# SirenSchematic.net
KiCad netlist of a schematic drawn in Altium Designer
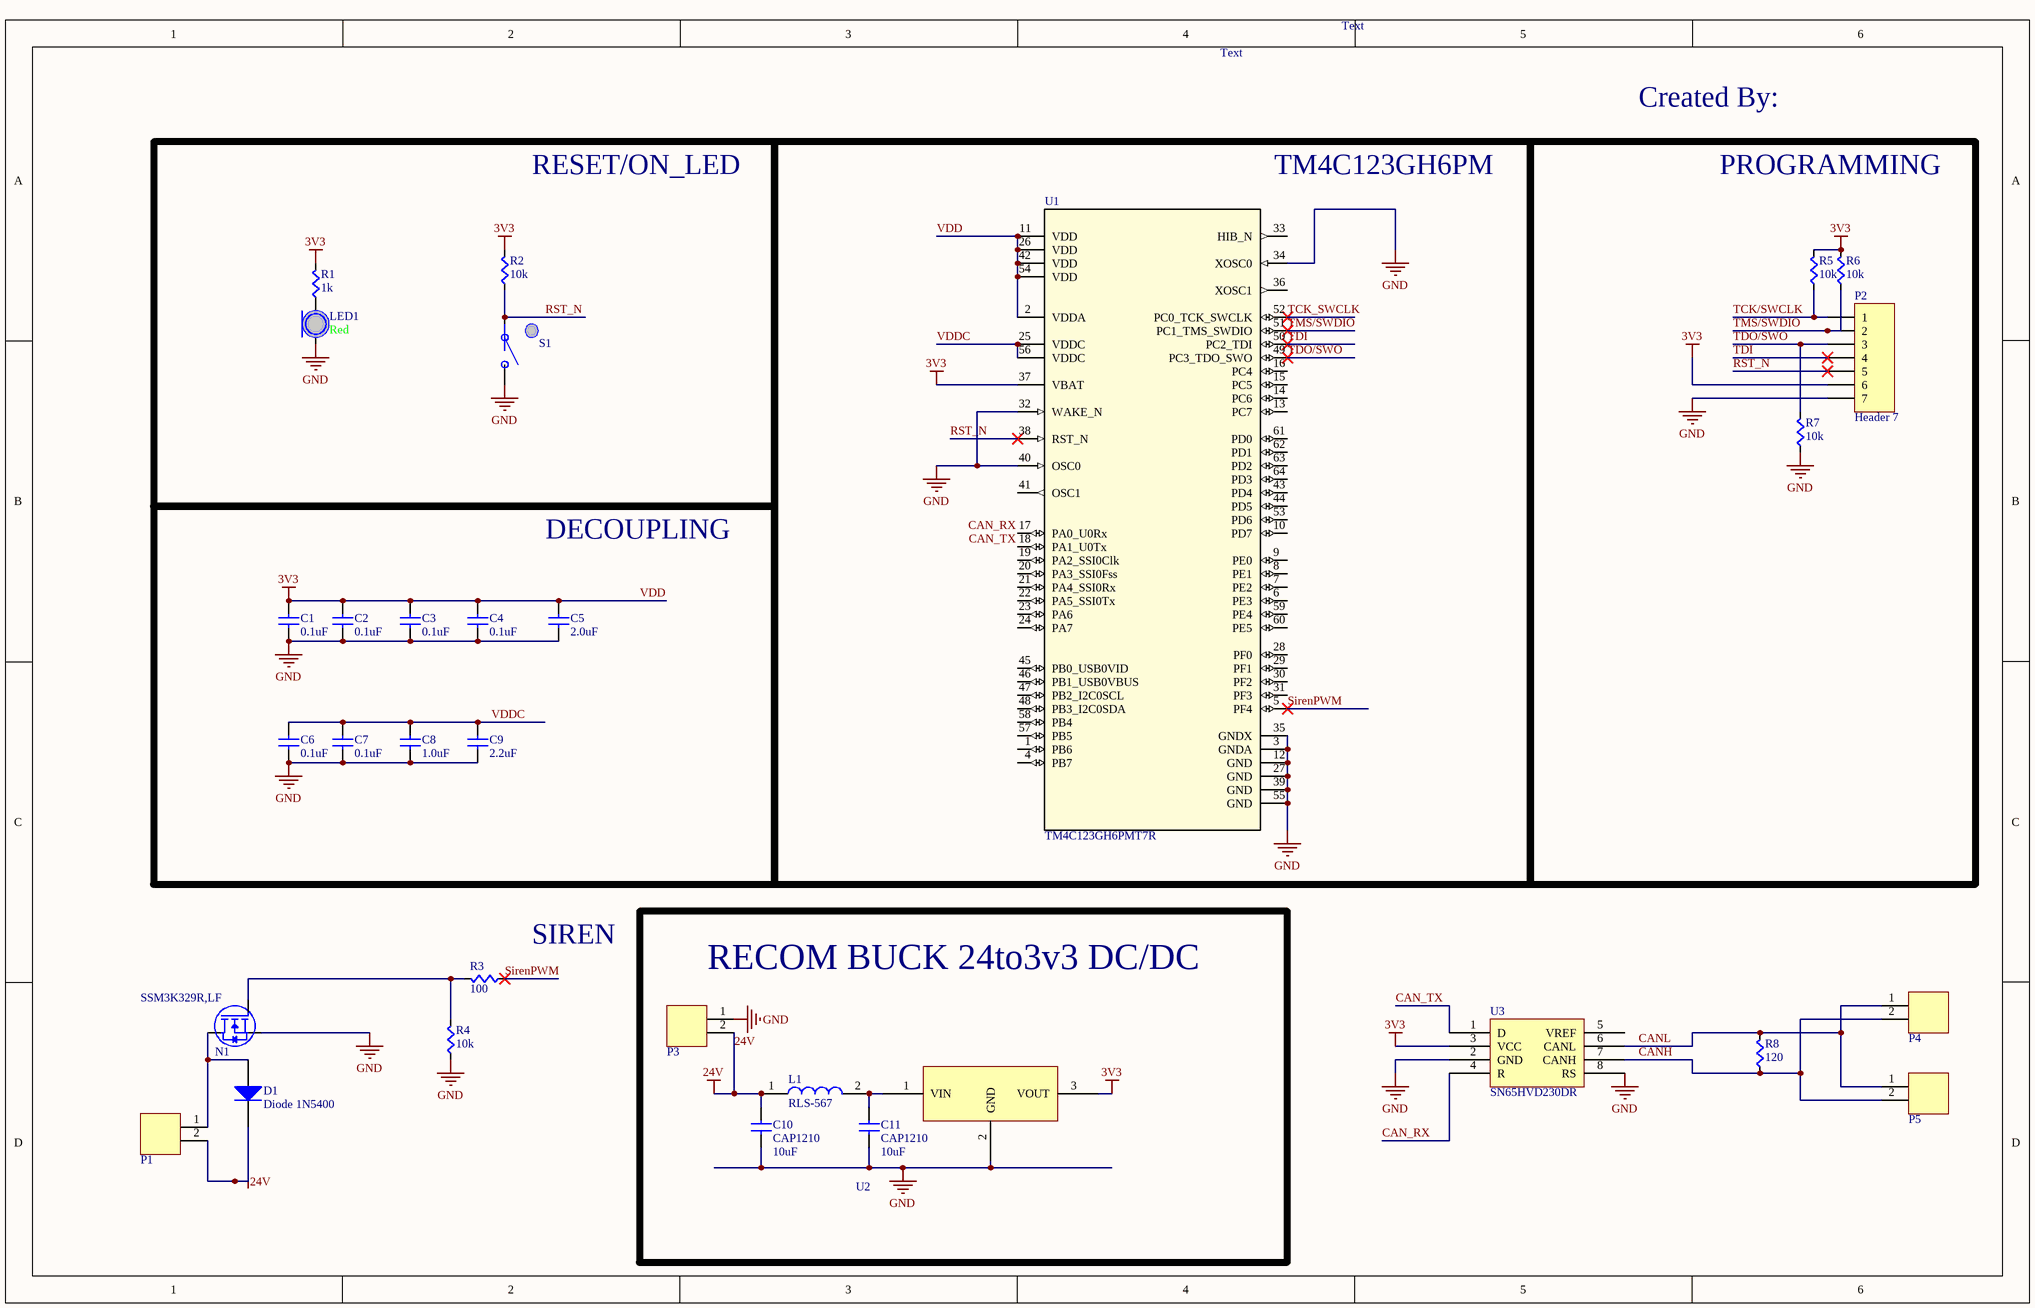
[diagram p0: SirenSchematic.SchDoc]

(export (version "E")
  (design (tool "Eeschema 10.0.6"))
  (components
    (comp (ref "C1")
      (value "0.1uF")
      (footprint "CAPC0603")
      (fields (field (name "Comment") "Cap"))
      (libsource (lib "SubjuGator8") (part "Cap"))
    )
    (comp (ref "C2")
      (value "0.1uF")
      (footprint "CAPC0603")
      (fields (field (name "Comment") "Cap"))
      (libsource (lib "SubjuGator8") (part "Cap"))
    )
    (comp (ref "C3")
      (value "0.1uF")
      (footprint "CAPC0603")
      (fields (field (name "Comment") "Cap"))
      (libsource (lib "SubjuGator8") (part "Cap"))
    )
    (comp (ref "C4")
      (value "0.1uF")
      (footprint "CAPC0603")
      (fields (field (name "Comment") "Cap"))
      (libsource (lib "SubjuGator8") (part "Cap"))
    )
    (comp (ref "C5")
      (value "2.0uF")
      (footprint "CAPC0603")
      (fields (field (name "Comment") "Cap"))
      (libsource (lib "SubjuGator8") (part "Cap"))
    )
    (comp (ref "C6")
      (value "0.1uF")
      (footprint "CAPC0603")
      (fields (field (name "Comment") "Cap"))
      (libsource (lib "SubjuGator8") (part "Cap"))
    )
    (comp (ref "C7")
      (value "0.1uF")
      (footprint "CAPC0603")
      (fields (field (name "Comment") "Cap"))
      (libsource (lib "SubjuGator8") (part "Cap"))
    )
    (comp (ref "C8")
      (value "1.0uF")
      (footprint "CAPC0603")
      (fields (field (name "Comment") "Cap"))
      (libsource (lib "SubjuGator8") (part "Cap"))
    )
    (comp (ref "C9")
      (value "2.2uF")
      (footprint "CAPC0603")
      (fields (field (name "Comment") "Cap"))
      (libsource (lib "SubjuGator8") (part "Cap"))
    )
    (comp (ref "C10")
      (value "CAP1210")
      (footprint "CAP1210")
      (description "CAP CER 10UF 50V 20% X5R 1210")
      (fields (field (name "ALTIUM_VALUE") "10uF"))
      (libsource (lib "SubjuGator8") (part "CAP1210"))
    )
    (comp (ref "C11")
      (value "CAP1210")
      (footprint "CAP1210")
      (description "CAP CER 10UF 50V 20% X5R 1210")
      (fields (field (name "ALTIUM_VALUE") "10uF"))
      (libsource (lib "SubjuGator8") (part "CAP1210"))
    )
    (comp (ref "D1")
      (value "Diode 1N5400")
      (footprint "DO-201AD")
      (description "3 Amp General Purpose Rectifier")
      (fields (field (name "PUBLISHER") "Altium Limited"))
      (libsource (lib "Miscellaneous Devices") (part "Diode 1N5400"))
    )
    (comp (ref "L1")
      (value "RLS-567")
      (footprint "*IND_RLS-567")
      (description "Inductor")
      (fields (field (name "MOUSER PART NUMBER") "919-RLS-567"))
      (libsource (lib "SubjuGator8") (part "RLS-567"))
    )
    (comp (ref "LED1")
      (value "LED")
      (footprint "LED0603")
      (fields (field (name "COLOR") "Red"))
      (libsource (lib "SubjuGator8") (part "LED"))
    )
    (comp (ref "N1")
      (value "SSM3K329R,LF")
      (footprint "SSM3K329R,LF")
      (description "MOSFET N CH 30V 3.5A 2-3Z1A")
      (libsource (lib "SubjuGator8") (part "SSM3K329R,LF"))
    )
    (comp (ref "P1")
      (value "2-pin Horz Sherlock")
      (footprint "MOLEX-HDR-1X2-SHERLOCK-HORZ")
      (fields
        (field (name "MANUFACTURER PART NUMBER") "0353630260")
        (field (name "MANUFACTURER") "Molex Inc")
      )
      (libsource (lib "SubjuGator8") (part "MOLEX-HDR-1x2-SHERLOCK_RA"))
    )
    (comp (ref "P2")
      (value "Header 7")
      (footprint "HDR1X7")
      (description "Header, 7-Pin")
      (fields (field (name "PUBLISHER") "Altium Limited"))
      (libsource (lib "Miscellaneous Connectors") (part "Header 7"))
    )
    (comp (ref "P3")
      (value "2-pin Horz Sherlock")
      (footprint "MOLEX-HDR-1X2-SHERLOCK-HORZ")
      (fields
        (field (name "MANUFACTURER PART NUMBER") "0353630260")
        (field (name "MANUFACTURER") "Molex Inc")
      )
      (libsource (lib "SubjuGator8") (part "MOLEX-HDR-1x2-SHERLOCK_RA"))
    )
    (comp (ref "P4")
      (value "2-pin Horz Sherlock")
      (footprint "MOLEX-HDR-1X2-SHERLOCK-HORZ")
      (fields
        (field (name "MANUFACTURER PART NUMBER") "0353630260")
        (field (name "MANUFACTURER") "Molex Inc")
      )
      (libsource (lib "") (part "MOLEX-HDR-1x2-SHERLOCK_RA_1"))
    )
    (comp (ref "P5")
      (value "2-pin Horz Sherlock")
      (footprint "MOLEX-HDR-1X2-SHERLOCK-HORZ")
      (fields
        (field (name "MANUFACTURER PART NUMBER") "0353630260")
        (field (name "MANUFACTURER") "Molex Inc")
      )
      (libsource (lib "") (part "MOLEX-HDR-1x2-SHERLOCK_RA_1"))
    )
    (comp (ref "R1")
      (value "1k")
      (footprint "RES0603")
      (fields (field (name "Comment") "Res"))
      (libsource (lib "SubjuGator8") (part "Res"))
    )
    (comp (ref "R2")
      (value "10k")
      (footprint "RES0603")
      (fields (field (name "Comment") "Res"))
      (libsource (lib "SubjuGator8") (part "Res"))
    )
    (comp (ref "R3")
      (value "100")
      (footprint "RES0603")
      (fields (field (name "Comment") "Res"))
      (libsource (lib "SubjuGator8") (part "Res"))
    )
    (comp (ref "R4")
      (value "10k")
      (footprint "RES0603")
      (fields (field (name "Comment") "Res"))
      (libsource (lib "SubjuGator8") (part "Res"))
    )
    (comp (ref "R5")
      (value "10k")
      (footprint "RES0603")
      (fields (field (name "Comment") "Res"))
      (libsource (lib "SubjuGator8") (part "Res"))
    )
    (comp (ref "R6")
      (value "10k")
      (footprint "RES0603")
      (fields (field (name "Comment") "Res"))
      (libsource (lib "SubjuGator8") (part "Res"))
    )
    (comp (ref "R7")
      (value "10k")
      (footprint "RES0603")
      (fields (field (name "Comment") "Res"))
      (libsource (lib "SubjuGator8") (part "Res"))
    )
    (comp (ref "R8")
      (value "120")
      (footprint "RES0603")
      (fields (field (name "Comment") "Res"))
      (libsource (lib "SubjuGator8") (part "Res"))
    )
    (comp (ref "S1")
      (value "Button")
      (footprint "PTS645xxxxSMTR92")
      (description "SPST Button")
      (libsource (lib "SubjuGator8") (part "Button"))
    )
    (comp (ref "U1")
      (value "TM4C123GH6PMT7R")
      (footprint "PM0064A_N")
      (description "Imported")
      (fields
        (field (name "PARTNUMBER") "TM4C123GH6PMTR")
        (field (name "ALTERNATE_PARTNUMBER") "TM4C123GH6PMT")
      )
      (libsource (lib "2018-10-31_17-53-54") (part "TM4C123GH6PMT7R"))
    )
    (comp (ref "U2")
      (value "R-78C3.3-1.0")
      (footprint "R-78C3.3-1.0")
      (description "CONV DC/DC 1A 3.3V OUT SIP VERT")
      (libsource (lib "SubjuGator8") (part "R-78C3.3-1.0"))
    )
    (comp (ref "U3")
      (value "SN65HVD230DR")
      (footprint "SOIC-8pin")
      (description "IC TXRX CAN 1MBPS 3.3V 8SOIC")
      (libsource (lib "SubjuGator8") (part "SN65HVD230DR"))
    )
  )
  (nets
    (net (code "1") (name "/CANH") (class "Default")
      (node (ref "P4") (pin "2") (pinfunction "2_2") (pintype "passive"))
      (node (ref "P5") (pin "2") (pinfunction "2_2") (pintype "passive"))
      (node (ref "R8") (pin "2") (pinfunction "B_2") (pintype "passive"))
      (node (ref "U3") (pin "7") (pinfunction "CANH_7") (pintype "passive"))
    )
    (net (code "2") (name "/CANL") (class "Default")
      (node (ref "P4") (pin "1") (pinfunction "1_1") (pintype "passive"))
      (node (ref "P5") (pin "1") (pinfunction "1_1") (pintype "passive"))
      (node (ref "R8") (pin "1") (pinfunction "A_1") (pintype "passive"))
      (node (ref "U3") (pin "6") (pinfunction "CANL_6") (pintype "passive"))
    )
    (net (code "3") (name "/CAN_RX") (class "Default")
      (node (ref "U1") (pin "17") (pinfunction "PA0_U0Rx_17") (pintype "bidirectional"))
      (node (ref "U3") (pin "4") (pinfunction "R_4") (pintype "passive"))
    )
    (net (code "4") (name "/CAN_TX") (class "Default")
      (node (ref "U1") (pin "18") (pinfunction "PA1_U0Tx_18") (pintype "bidirectional"))
      (node (ref "U3") (pin "1") (pinfunction "D_1") (pintype "passive"))
    )
    (net (code "5") (name "/RST_N") (class "Default")
      (node (ref "P2") (pin "5") (pinfunction "5_5") (pintype "passive"))
      (node (ref "R2") (pin "2") (pinfunction "B_2") (pintype "passive"))
      (node (ref "S1") (pin "A") (pinfunction "A_A") (pintype "passive"))
      (node (ref "U1") (pin "38") (pinfunction "RST_N_38") (pintype "input"))
    )
    (net (code "6") (name "/SirenPWM") (class "Default")
      (node (ref "R3") (pin "2") (pinfunction "B_2") (pintype "passive"))
      (node (ref "U1") (pin "5") (pinfunction "PF4_5") (pintype "bidirectional"))
    )
    (net (code "7") (name "/TCK_SWCLK") (class "Default")
      (node (ref "U1") (pin "52") (pinfunction "PC0_TCK_SWCLK_52") (pintype "bidirectional+no_connect"))
    )
    (net (code "8") (name "/TCK{slash}SWCLK") (class "Default")
      (node (ref "P2") (pin "1") (pinfunction "1_1") (pintype "passive"))
      (node (ref "R5") (pin "2") (pinfunction "B_2") (pintype "passive"))
    )
    (net (code "9") (name "/TDI") (class "Default")
      (node (ref "P2") (pin "4") (pinfunction "4_4") (pintype "passive"))
      (node (ref "U1") (pin "50") (pinfunction "PC2_TDI_50") (pintype "bidirectional"))
    )
    (net (code "10") (name "/TDO{slash}SWO") (class "Default")
      (node (ref "P2") (pin "3") (pinfunction "3_3") (pintype "passive"))
      (node (ref "R7") (pin "1") (pinfunction "A_1") (pintype "passive"))
      (node (ref "U1") (pin "49") (pinfunction "PC3_TDO_SWO_49") (pintype "bidirectional"))
    )
    (net (code "11") (name "/TMS{slash}SWDIO") (class "Default")
      (node (ref "P2") (pin "2") (pinfunction "2_2") (pintype "passive"))
      (node (ref "R6") (pin "2") (pinfunction "B_2") (pintype "passive"))
      (node (ref "U1") (pin "51") (pinfunction "PC1_TMS_SWDIO_51") (pintype "bidirectional"))
    )
    (net (code "12") (name "/VDDC") (class "Default")
      (node (ref "C6") (pin "1") (pinfunction "A_1") (pintype "passive"))
      (node (ref "C7") (pin "1") (pinfunction "A_1") (pintype "passive"))
      (node (ref "C8") (pin "1") (pinfunction "A_1") (pintype "passive"))
      (node (ref "C9") (pin "1") (pinfunction "A_1") (pintype "passive"))
      (node (ref "U1") (pin "25") (pinfunction "VDDC_25") (pintype "power_in"))
      (node (ref "U1") (pin "56") (pinfunction "VDDC_56") (pintype "power_in"))
    )
    (net (code "13") (name "3V3") (class "Default")
      (node (ref "C1") (pin "1") (pinfunction "A_1") (pintype "passive"))
      (node (ref "C2") (pin "1") (pinfunction "A_1") (pintype "passive"))
      (node (ref "C3") (pin "1") (pinfunction "A_1") (pintype "passive"))
      (node (ref "C4") (pin "1") (pinfunction "A_1") (pintype "passive"))
      (node (ref "C5") (pin "1") (pinfunction "A_1") (pintype "passive"))
      (node (ref "P2") (pin "6") (pinfunction "6_6") (pintype "passive"))
      (node (ref "R1") (pin "1") (pinfunction "A_1") (pintype "passive"))
      (node (ref "R2") (pin "1") (pinfunction "A_1") (pintype "passive"))
      (node (ref "R5") (pin "1") (pinfunction "A_1") (pintype "passive"))
      (node (ref "R6") (pin "1") (pinfunction "A_1") (pintype "passive"))
      (node (ref "U1") (pin "11") (pinfunction "VDD_11") (pintype "power_in"))
      (node (ref "U1") (pin "2") (pinfunction "VDDA_2") (pintype "power_in"))
      (node (ref "U1") (pin "26") (pinfunction "VDD_26") (pintype "power_in"))
      (node (ref "U1") (pin "37") (pinfunction "VBAT_37") (pintype "power_in"))
      (node (ref "U1") (pin "42") (pinfunction "VDD_42") (pintype "power_in"))
      (node (ref "U1") (pin "54") (pinfunction "VDD_54") (pintype "power_in"))
      (node (ref "U2") (pin "3") (pinfunction "VOUT_3") (pintype "passive"))
      (node (ref "U3") (pin "3") (pinfunction "VCC_3") (pintype "passive"))
    )
    (net (code "14") (name "24V") (class "Default")
      (node (ref "C10") (pin "1") (pinfunction "A_1") (pintype "passive"))
      (node (ref "D1") (pin "2") (pinfunction "K_2") (pintype "passive"))
      (node (ref "L1") (pin "1") (pinfunction "1_1") (pintype "passive"))
      (node (ref "P1") (pin "2") (pinfunction "2_2") (pintype "passive"))
      (node (ref "P3") (pin "2") (pinfunction "2_2") (pintype "passive"))
    )
    (net (code "15") (name "GND") (class "Default")
      (node (ref "C1") (pin "2") (pinfunction "B_2") (pintype "passive"))
      (node (ref "C10") (pin "2") (pinfunction "B_2") (pintype "passive"))
      (node (ref "C11") (pin "2") (pinfunction "B_2") (pintype "passive"))
      (node (ref "C2") (pin "2") (pinfunction "B_2") (pintype "passive"))
      (node (ref "C3") (pin "2") (pinfunction "B_2") (pintype "passive"))
      (node (ref "C4") (pin "2") (pinfunction "B_2") (pintype "passive"))
      (node (ref "C5") (pin "2") (pinfunction "B_2") (pintype "passive"))
      (node (ref "C6") (pin "2") (pinfunction "B_2") (pintype "passive"))
      (node (ref "C7") (pin "2") (pinfunction "B_2") (pintype "passive"))
      (node (ref "C8") (pin "2") (pinfunction "B_2") (pintype "passive"))
      (node (ref "C9") (pin "2") (pinfunction "B_2") (pintype "passive"))
      (node (ref "LED1") (pin "C") (pinfunction "C_C") (pintype "passive"))
      (node (ref "N1") (pin "2") (pinfunction "S_2") (pintype "passive"))
      (node (ref "P2") (pin "7") (pinfunction "7_7") (pintype "passive"))
      (node (ref "P3") (pin "1") (pinfunction "1_1") (pintype "passive"))
      (node (ref "R4") (pin "2") (pinfunction "B_2") (pintype "passive"))
      (node (ref "R7") (pin "2") (pinfunction "B_2") (pintype "passive"))
      (node (ref "S1") (pin "B") (pinfunction "B_B") (pintype "passive"))
      (node (ref "U1") (pin "12") (pinfunction "GND_12") (pintype "power_in"))
      (node (ref "U1") (pin "27") (pinfunction "GND_27") (pintype "power_in"))
      (node (ref "U1") (pin "3") (pinfunction "GNDA_3") (pintype "power_in"))
      (node (ref "U1") (pin "32") (pinfunction "WAKE_N_32") (pintype "input"))
      (node (ref "U1") (pin "34") (pinfunction "XOSC0_34") (pintype "input"))
      (node (ref "U1") (pin "35") (pinfunction "GNDX_35") (pintype "power_in"))
      (node (ref "U1") (pin "39") (pinfunction "GND_39") (pintype "power_in"))
      (node (ref "U1") (pin "40") (pinfunction "OSC0_40") (pintype "input"))
      (node (ref "U1") (pin "55") (pinfunction "GND_55") (pintype "power_in"))
      (node (ref "U2") (pin "2") (pinfunction "GND_2") (pintype "power_in"))
      (node (ref "U3") (pin "2") (pinfunction "GND_2") (pintype "passive"))
      (node (ref "U3") (pin "8") (pinfunction "RS_8") (pintype "passive"))
    )
    (net (code "16") (name "Net-(C11-A)") (class "Default")
      (node (ref "C11") (pin "1") (pinfunction "A_1") (pintype "passive"))
      (node (ref "L1") (pin "2") (pinfunction "2_2") (pintype "passive"))
      (node (ref "U2") (pin "1") (pinfunction "VIN_1") (pintype "passive"))
    )
    (net (code "17") (name "Net-(D1-A)") (class "Default")
      (node (ref "D1") (pin "1") (pinfunction "A_1") (pintype "passive"))
      (node (ref "N1") (pin "3") (pinfunction "D_3") (pintype "passive"))
      (node (ref "P1") (pin "1") (pinfunction "1_1") (pintype "passive"))
    )
    (net (code "18") (name "Net-(N1-G)") (class "Default")
      (node (ref "N1") (pin "1") (pinfunction "G_1") (pintype "passive"))
      (node (ref "R3") (pin "1") (pinfunction "A_1") (pintype "passive"))
      (node (ref "R4") (pin "1") (pinfunction "A_1") (pintype "passive"))
    )
    (net (code "19") (name "Net-(R1-B)") (class "Default")
      (node (ref "LED1") (pin "A") (pinfunction "A_A") (pintype "passive"))
      (node (ref "R1") (pin "2") (pinfunction "B_2") (pintype "passive"))
    )
    (net (code "20") (name "unconnected-(U1-HIB_N-Pad33)") (class "Default")
      (node (ref "U1") (pin "33") (pinfunction "HIB_N_33") (pintype "output"))
    )
    (net (code "21") (name "unconnected-(U1-OSC1-Pad41)") (class "Default")
      (node (ref "U1") (pin "41") (pinfunction "OSC1_41") (pintype "output"))
    )
    (net (code "22") (name "unconnected-(U1-PA2_SSI0Clk-Pad19)") (class "Default")
      (node (ref "U1") (pin "19") (pinfunction "PA2_SSI0Clk_19") (pintype "bidirectional"))
    )
    (net (code "23") (name "unconnected-(U1-PA3_SSI0Fss-Pad20)") (class "Default")
      (node (ref "U1") (pin "20") (pinfunction "PA3_SSI0Fss_20") (pintype "bidirectional"))
    )
    (net (code "24") (name "unconnected-(U1-PA4_SSI0Rx-Pad21)") (class "Default")
      (node (ref "U1") (pin "21") (pinfunction "PA4_SSI0Rx_21") (pintype "bidirectional"))
    )
    (net (code "25") (name "unconnected-(U1-PA5_SSI0Tx-Pad22)") (class "Default")
      (node (ref "U1") (pin "22") (pinfunction "PA5_SSI0Tx_22") (pintype "bidirectional"))
    )
    (net (code "26") (name "unconnected-(U1-PA6-Pad23)") (class "Default")
      (node (ref "U1") (pin "23") (pinfunction "PA6_23") (pintype "bidirectional"))
    )
    (net (code "27") (name "unconnected-(U1-PA7-Pad24)") (class "Default")
      (node (ref "U1") (pin "24") (pinfunction "PA7_24") (pintype "bidirectional"))
    )
    (net (code "28") (name "unconnected-(U1-PB0_USB0VID-Pad45)") (class "Default")
      (node (ref "U1") (pin "45") (pinfunction "PB0_USB0VID_45") (pintype "bidirectional"))
    )
    (net (code "29") (name "unconnected-(U1-PB1_USB0VBUS-Pad46)") (class "Default")
      (node (ref "U1") (pin "46") (pinfunction "PB1_USB0VBUS_46") (pintype "bidirectional"))
    )
    (net (code "30") (name "unconnected-(U1-PB2_I2C0SCL-Pad47)") (class "Default")
      (node (ref "U1") (pin "47") (pinfunction "PB2_I2C0SCL_47") (pintype "bidirectional"))
    )
    (net (code "31") (name "unconnected-(U1-PB3_I2C0SDA-Pad48)") (class "Default")
      (node (ref "U1") (pin "48") (pinfunction "PB3_I2C0SDA_48") (pintype "bidirectional"))
    )
    (net (code "32") (name "unconnected-(U1-PB4-Pad58)") (class "Default")
      (node (ref "U1") (pin "58") (pinfunction "PB4_58") (pintype "bidirectional"))
    )
    (net (code "33") (name "unconnected-(U1-PB5-Pad57)") (class "Default")
      (node (ref "U1") (pin "57") (pinfunction "PB5_57") (pintype "bidirectional"))
    )
    (net (code "34") (name "unconnected-(U1-PB6-Pad1)") (class "Default")
      (node (ref "U1") (pin "1") (pinfunction "PB6_1") (pintype "bidirectional"))
    )
    (net (code "35") (name "unconnected-(U1-PB7-Pad4)") (class "Default")
      (node (ref "U1") (pin "4") (pinfunction "PB7_4") (pintype "bidirectional"))
    )
    (net (code "36") (name "unconnected-(U1-PC4-Pad16)") (class "Default")
      (node (ref "U1") (pin "16") (pinfunction "PC4_16") (pintype "bidirectional"))
    )
    (net (code "37") (name "unconnected-(U1-PC5-Pad15)") (class "Default")
      (node (ref "U1") (pin "15") (pinfunction "PC5_15") (pintype "bidirectional"))
    )
    (net (code "38") (name "unconnected-(U1-PC6-Pad14)") (class "Default")
      (node (ref "U1") (pin "14") (pinfunction "PC6_14") (pintype "bidirectional"))
    )
    (net (code "39") (name "unconnected-(U1-PC7-Pad13)") (class "Default")
      (node (ref "U1") (pin "13") (pinfunction "PC7_13") (pintype "bidirectional"))
    )
    (net (code "40") (name "unconnected-(U1-PD0-Pad61)") (class "Default")
      (node (ref "U1") (pin "61") (pinfunction "PD0_61") (pintype "bidirectional"))
    )
    (net (code "41") (name "unconnected-(U1-PD1-Pad62)") (class "Default")
      (node (ref "U1") (pin "62") (pinfunction "PD1_62") (pintype "bidirectional"))
    )
    (net (code "42") (name "unconnected-(U1-PD2-Pad63)") (class "Default")
      (node (ref "U1") (pin "63") (pinfunction "PD2_63") (pintype "bidirectional"))
    )
    (net (code "43") (name "unconnected-(U1-PD3-Pad64)") (class "Default")
      (node (ref "U1") (pin "64") (pinfunction "PD3_64") (pintype "bidirectional"))
    )
    (net (code "44") (name "unconnected-(U1-PD4-Pad43)") (class "Default")
      (node (ref "U1") (pin "43") (pinfunction "PD4_43") (pintype "bidirectional"))
    )
    (net (code "45") (name "unconnected-(U1-PD5-Pad44)") (class "Default")
      (node (ref "U1") (pin "44") (pinfunction "PD5_44") (pintype "bidirectional"))
    )
    (net (code "46") (name "unconnected-(U1-PD6-Pad53)") (class "Default")
      (node (ref "U1") (pin "53") (pinfunction "PD6_53") (pintype "bidirectional"))
    )
    (net (code "47") (name "unconnected-(U1-PD7-Pad10)") (class "Default")
      (node (ref "U1") (pin "10") (pinfunction "PD7_10") (pintype "bidirectional"))
    )
    (net (code "48") (name "unconnected-(U1-PE0-Pad9)") (class "Default")
      (node (ref "U1") (pin "9") (pinfunction "PE0_9") (pintype "bidirectional"))
    )
    (net (code "49") (name "unconnected-(U1-PE1-Pad8)") (class "Default")
      (node (ref "U1") (pin "8") (pinfunction "PE1_8") (pintype "bidirectional"))
    )
    (net (code "50") (name "unconnected-(U1-PE2-Pad7)") (class "Default")
      (node (ref "U1") (pin "7") (pinfunction "PE2_7") (pintype "bidirectional"))
    )
    (net (code "51") (name "unconnected-(U1-PE3-Pad6)") (class "Default")
      (node (ref "U1") (pin "6") (pinfunction "PE3_6") (pintype "bidirectional"))
    )
    (net (code "52") (name "unconnected-(U1-PE4-Pad59)") (class "Default")
      (node (ref "U1") (pin "59") (pinfunction "PE4_59") (pintype "bidirectional"))
    )
    (net (code "53") (name "unconnected-(U1-PE5-Pad60)") (class "Default")
      (node (ref "U1") (pin "60") (pinfunction "PE5_60") (pintype "bidirectional"))
    )
    (net (code "54") (name "unconnected-(U1-PF0-Pad28)") (class "Default")
      (node (ref "U1") (pin "28") (pinfunction "PF0_28") (pintype "bidirectional"))
    )
    (net (code "55") (name "unconnected-(U1-PF1-Pad29)") (class "Default")
      (node (ref "U1") (pin "29") (pinfunction "PF1_29") (pintype "bidirectional"))
    )
    (net (code "56") (name "unconnected-(U1-PF2-Pad30)") (class "Default")
      (node (ref "U1") (pin "30") (pinfunction "PF2_30") (pintype "bidirectional"))
    )
    (net (code "57") (name "unconnected-(U1-PF3-Pad31)") (class "Default")
      (node (ref "U1") (pin "31") (pinfunction "PF3_31") (pintype "bidirectional"))
    )
    (net (code "58") (name "unconnected-(U1-XOSC1-Pad36)") (class "Default")
      (node (ref "U1") (pin "36") (pinfunction "XOSC1_36") (pintype "output"))
    )
    (net (code "59") (name "unconnected-(U3-VREF-Pad5)") (class "Default")
      (node (ref "U3") (pin "5") (pinfunction "VREF_5") (pintype "passive"))
    )
  )
)
